# Main.net
KiCad netlist of a schematic drawn in Altium Designer
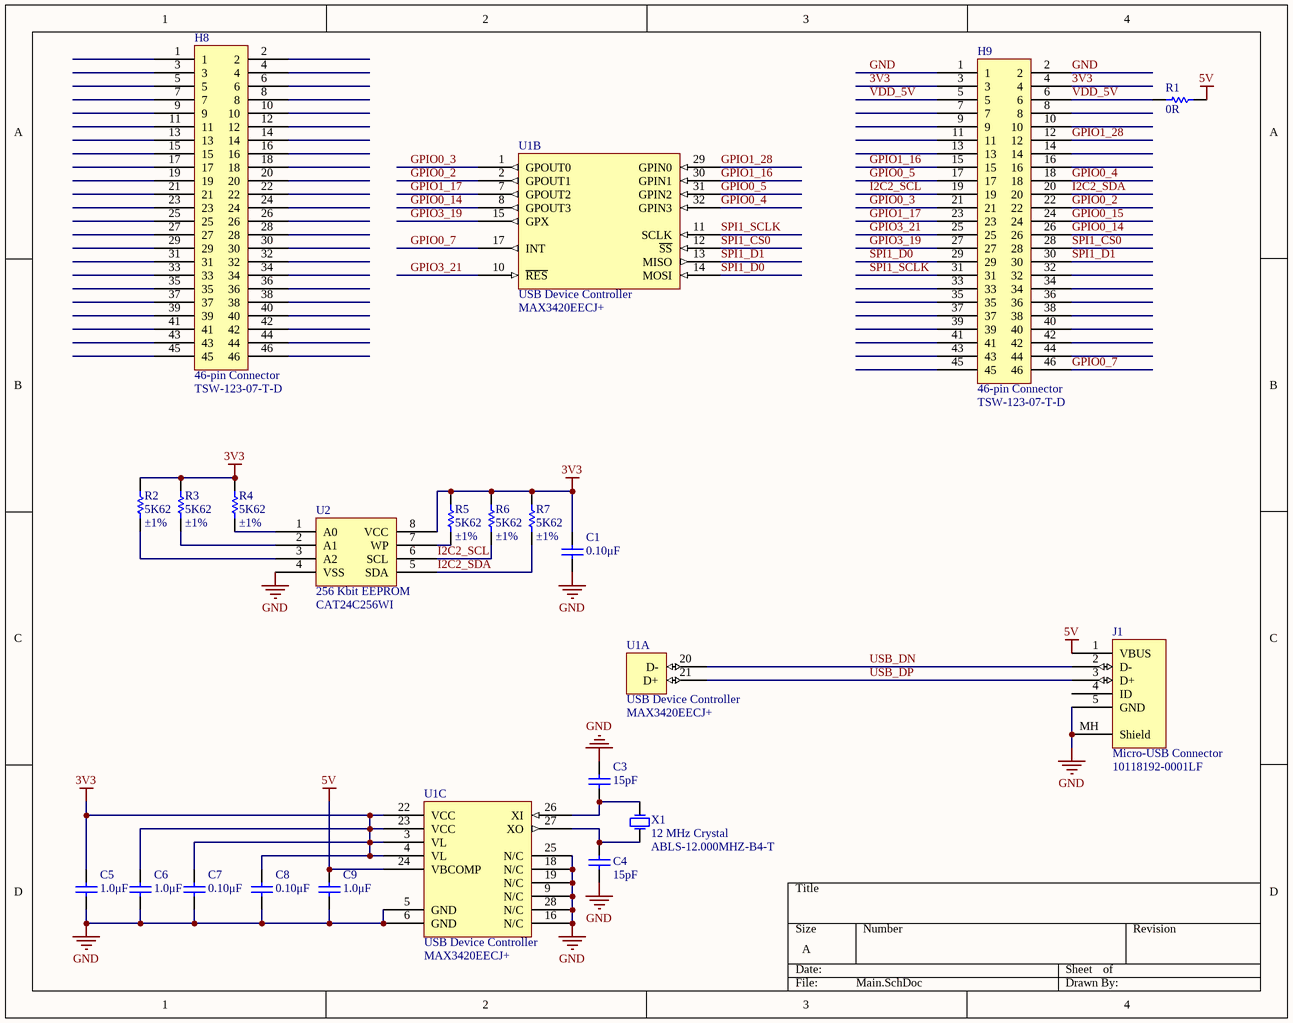
[diagram p0: Main.SchDoc]

(export (version "E")
  (design (tool "Eeschema 10.0.6"))
  (components
    (comp (ref "C1")
      (value "0.10μF")
      (footprint "0805_100")
      (description "CAP 0.10μF  0805 16V   ±10%    X7R")
      (fields (field (name "MANUFACTURER") "Murata") (field (name "PARTNUMBER") "GRM21BR71C104KA01#"))
      (libsource (lib "0805_Cap_GRM") (part "GRM21BR71C104KA01#"))
    )
    (comp (ref "C3")
      (value "15pF")
      (footprint "0805_100")
      (description "CAP 15pF     0805 250V  ±5%     C0G")
      (fields (field (name "MANUFACTURER") "Murata") (field (name "PARTNUMBER") "GRM21A5C2E150JW01#"))
      (libsource (lib "0805_Cap_GRM") (part "GRM21A5C2E150JW01#"))
    )
    (comp (ref "C4")
      (value "15pF")
      (footprint "0805_100")
      (description "CAP 15pF     0805 250V  ±5%     C0G")
      (fields (field (name "MANUFACTURER") "Murata") (field (name "PARTNUMBER") "GRM21A5C2E150JW01#"))
      (libsource (lib "0805_Cap_GRM") (part "GRM21A5C2E150JW01#"))
    )
    (comp (ref "C5")
      (value "1.0μF")
      (footprint "0805_100")
      (description "CAP 1.0μF   0805 16V   ±10%    X7R")
      (fields (field (name "MANUFACTURER") "Murata") (field (name "PARTNUMBER") "GRM21BR71C105KA01#"))
      (libsource (lib "0805_Cap_GRM") (part "GRM21BR71C105KA01#"))
    )
    (comp (ref "C6")
      (value "1.0μF")
      (footprint "0805_100")
      (description "CAP 1.0μF   0805 16V   ±10%    X7R")
      (fields (field (name "MANUFACTURER") "Murata") (field (name "PARTNUMBER") "GRM21BR71C105KA01#"))
      (libsource (lib "0805_Cap_GRM") (part "GRM21BR71C105KA01#"))
    )
    (comp (ref "C7")
      (value "0.10μF")
      (footprint "0805_100")
      (description "CAP 0.10μF  0805 16V   ±10%    X7R")
      (fields (field (name "MANUFACTURER") "Murata") (field (name "PARTNUMBER") "GRM21BR71C104KA01#"))
      (libsource (lib "0805_Cap_GRM") (part "GRM21BR71C104KA01#"))
    )
    (comp (ref "C8")
      (value "0.10μF")
      (footprint "0805_100")
      (description "CAP 0.10μF  0805 16V   ±10%    X7R")
      (fields (field (name "MANUFACTURER") "Murata") (field (name "PARTNUMBER") "GRM21BR71C104KA01#"))
      (libsource (lib "0805_Cap_GRM") (part "GRM21BR71C104KA01#"))
    )
    (comp (ref "C9")
      (value "1.0μF")
      (footprint "0805_100")
      (description "CAP 1.0μF   0805 16V   ±10%    X7R")
      (fields (field (name "MANUFACTURER") "Murata") (field (name "PARTNUMBER") "GRM21BR71C105KA01#"))
      (libsource (lib "0805_Cap_GRM") (part "GRM21BR71C105KA01#"))
    )
    (comp (ref "H8")
      (value "46-pin Connector")
      (footprint "TSW-123-07-X-S")
      (description "46-pin Dual Row 100-mil Headers")
      (fields (field (name "MANUFACTURER") "Samtec") (field (name "PARTNUMBER") "TSW-123-07-T-D"))
      (libsource (lib "Samtec") (part "TSW-123-07-T-D"))
    )
    (comp (ref "H9")
      (value "46-pin Connector")
      (footprint "TSW-123-07-X-S")
      (description "46-pin Dual Row 100-mil Headers")
      (fields (field (name "MANUFACTURER") "Samtec") (field (name "PARTNUMBER") "TSW-123-07-T-D"))
      (libsource (lib "Samtec") (part "TSW-123-07-T-D"))
    )
    (comp (ref "J1")
      (value "Micro-USB Connector")
      (footprint "10118192")
      (description "Surface-mount USB 2.0 Micro-B Connector with Flange")
      (fields (field (name "MANUFACTURER") "Amphenol") (field (name "PARTNUMBER") "10118192-0001LF"))
      (libsource (lib "Amphenol") (part "10118192-0001LF"))
    )
    (comp (ref "R1")
      (value "0R")
      (footprint "0805_75")
      (description "RES 0R 0805 2 A")
      (fields (field (name "PARTNUMBER") "ERJ-6GEY0R00V") (field (name "MANUFACTURER") "Panasonic"))
      (libsource (lib "0805_Res_ERJ") (part "ERJ-6GEY0R00V"))
    )
    (comp (ref "R2")
      (value "5K62")
      (footprint "0805_75")
      (description "RES 5K62 0805 ±1%")
      (fields
        (field (name "PARTNUMBER") "ERJ-6ENF5621V")
        (field (name "MANUFACTURER") "Panasonic")
        (field (name "TOLERANCE") "±1%")
      )
      (libsource (lib "0805_Res_ERJ") (part "ERJ-6ENF5621V"))
    )
    (comp (ref "R3")
      (value "5K62")
      (footprint "0805_75")
      (description "RES 5K62 0805 ±1%")
      (fields
        (field (name "PARTNUMBER") "ERJ-6ENF5621V")
        (field (name "MANUFACTURER") "Panasonic")
        (field (name "TOLERANCE") "±1%")
      )
      (libsource (lib "0805_Res_ERJ") (part "ERJ-6ENF5621V"))
    )
    (comp (ref "R4")
      (value "5K62")
      (footprint "0805_75")
      (description "RES 5K62 0805 ±1%")
      (fields
        (field (name "PARTNUMBER") "ERJ-6ENF5621V")
        (field (name "MANUFACTURER") "Panasonic")
        (field (name "TOLERANCE") "±1%")
      )
      (libsource (lib "0805_Res_ERJ") (part "ERJ-6ENF5621V"))
    )
    (comp (ref "R5")
      (value "5K62")
      (footprint "0805_75")
      (description "RES 5K62 0805 ±1%")
      (fields
        (field (name "PARTNUMBER") "ERJ-6ENF5621V")
        (field (name "MANUFACTURER") "Panasonic")
        (field (name "TOLERANCE") "±1%")
      )
      (libsource (lib "0805_Res_ERJ") (part "ERJ-6ENF5621V"))
    )
    (comp (ref "R6")
      (value "5K62")
      (footprint "0805_75")
      (description "RES 5K62 0805 ±1%")
      (fields
        (field (name "PARTNUMBER") "ERJ-6ENF5621V")
        (field (name "MANUFACTURER") "Panasonic")
        (field (name "TOLERANCE") "±1%")
      )
      (libsource (lib "0805_Res_ERJ") (part "ERJ-6ENF5621V"))
    )
    (comp (ref "R7")
      (value "5K62")
      (footprint "0805_75")
      (description "RES 5K62 0805 ±1%")
      (fields
        (field (name "PARTNUMBER") "ERJ-6ENF5621V")
        (field (name "MANUFACTURER") "Panasonic")
        (field (name "TOLERANCE") "±1%")
      )
      (libsource (lib "0805_Res_ERJ") (part "ERJ-6ENF5621V"))
    )
    (comp (ref "U1")
      (value "USB Device Controller")
      (footprint "C32+1")
      (description "USB Peripheral Controller with SPI Interface")
      (fields (field (name "MANUFACTURER") "Maxim IC") (field (name "PARTNUMBER") "MAX3420EECJ+"))
      (libsource (lib "Maxim") (part "MAX3420EEJC+"))
    )
    (comp (ref "U2")
      (value "256 Kbit EEPROM")
      (footprint "SOIC-8")
      (description "256 Kbit EEPROM Memory - I2C")
      (fields (field (name "MANUFACTURER") "ON-Semiconductor") (field (name "PARTNUMBER") "CAT24C256WI"))
      (libsource (lib "OnSemi") (part "CAT24C256WI"))
    )
    (comp (ref "X1")
      (value "12 MHz Crystal")
      (footprint "ABLS")
      (description "12 MHz 20 ppm Crystal")
      (fields (field (name "MANUFACTURER") "Abracon") (field (name "PARTNUMBER") "ABLS-12.000MHZ-B4-T"))
      (libsource (lib "Abracon") (part "ABLS-12.000MHZ-B4-T"))
    )
  )
  (nets
    (net (code "1") (name "/GPIO0_2") (class "Default")
      (node (ref "H9") (pin "22") (pinfunction "22_22") (pintype "passive"))
      (node (ref "U1") (pin "2") (pinfunction "GPOUT1_2") (pintype "output"))
    )
    (net (code "2") (name "/GPIO0_3") (class "Default")
      (node (ref "H9") (pin "21") (pinfunction "21_21") (pintype "passive"))
      (node (ref "U1") (pin "1") (pinfunction "GPOUT0_1") (pintype "output"))
    )
    (net (code "3") (name "/GPIO0_4") (class "Default")
      (node (ref "H9") (pin "18") (pinfunction "18_18") (pintype "passive"))
      (node (ref "U1") (pin "32") (pinfunction "GPIN3_32") (pintype "input"))
    )
    (net (code "4") (name "/GPIO0_5") (class "Default")
      (node (ref "H9") (pin "17") (pinfunction "17_17") (pintype "passive"))
      (node (ref "U1") (pin "31") (pinfunction "GPIN2_31") (pintype "input"))
    )
    (net (code "5") (name "/GPIO0_7") (class "Default")
      (node (ref "H9") (pin "46") (pinfunction "46_46") (pintype "passive"))
      (node (ref "U1") (pin "17") (pinfunction "INT_17") (pintype "output"))
    )
    (net (code "6") (name "/GPIO0_14") (class "Default")
      (node (ref "H9") (pin "26") (pinfunction "26_26") (pintype "passive"))
      (node (ref "U1") (pin "8") (pinfunction "GPOUT3_8") (pintype "output"))
    )
    (net (code "7") (name "/GPIO0_15") (class "Default")
      (node (ref "H9") (pin "24") (pinfunction "24_24") (pintype "passive"))
    )
    (net (code "8") (name "/GPIO1_16") (class "Default")
      (node (ref "H9") (pin "15") (pinfunction "15_15") (pintype "passive"))
      (node (ref "U1") (pin "30") (pinfunction "GPIN1_30") (pintype "input"))
    )
    (net (code "9") (name "/GPIO1_17") (class "Default")
      (node (ref "H9") (pin "23") (pinfunction "23_23") (pintype "passive"))
      (node (ref "U1") (pin "7") (pinfunction "GPOUT2_7") (pintype "output"))
    )
    (net (code "10") (name "/GPIO1_28") (class "Default")
      (node (ref "H9") (pin "12") (pinfunction "12_12") (pintype "passive"))
      (node (ref "U1") (pin "29") (pinfunction "GPIN0_29") (pintype "input"))
    )
    (net (code "11") (name "/GPIO3_19") (class "Default")
      (node (ref "H9") (pin "27") (pinfunction "27_27") (pintype "passive"))
      (node (ref "U1") (pin "15") (pinfunction "GPX_15") (pintype "output"))
    )
    (net (code "12") (name "/GPIO3_21") (class "Default")
      (node (ref "H9") (pin "25") (pinfunction "25_25") (pintype "passive"))
      (node (ref "U1") (pin "10") (pinfunction "~{RES}_10") (pintype "input"))
    )
    (net (code "13") (name "/I2C2_SCL") (class "Default")
      (node (ref "H9") (pin "19") (pinfunction "19_19") (pintype "passive"))
      (node (ref "R6") (pin "1") (pinfunction "1_1") (pintype "passive"))
      (node (ref "U2") (pin "6") (pinfunction "SCL_6") (pintype "passive"))
    )
    (net (code "14") (name "/I2C2_SDA") (class "Default")
      (node (ref "H9") (pin "20") (pinfunction "20_20") (pintype "passive"))
      (node (ref "R7") (pin "1") (pinfunction "1_1") (pintype "passive"))
      (node (ref "U2") (pin "5") (pinfunction "SDA_5") (pintype "passive"))
    )
    (net (code "15") (name "/SPI1_CS0") (class "Default")
      (node (ref "H9") (pin "28") (pinfunction "28_28") (pintype "passive"))
      (node (ref "U1") (pin "12") (pinfunction "~{SS}_12") (pintype "input"))
    )
    (net (code "16") (name "/SPI1_D0") (class "Default")
      (node (ref "H9") (pin "29") (pinfunction "29_29") (pintype "passive"))
      (node (ref "U1") (pin "14") (pinfunction "MOSI_14") (pintype "input"))
    )
    (net (code "17") (name "/SPI1_D1") (class "Default")
      (node (ref "H9") (pin "30") (pinfunction "30_30") (pintype "passive"))
      (node (ref "U1") (pin "13") (pinfunction "MISO_13") (pintype "output"))
    )
    (net (code "18") (name "/SPI1_SCLK") (class "Default")
      (node (ref "H9") (pin "31") (pinfunction "31_31") (pintype "passive"))
      (node (ref "U1") (pin "11") (pinfunction "SCLK_11") (pintype "input"))
    )
    (net (code "19") (name "/USB_DN") (class "Default")
      (node (ref "J1") (pin "2") (pinfunction "D-_2") (pintype "bidirectional"))
      (node (ref "U1") (pin "20") (pinfunction "D-_20") (pintype "bidirectional"))
    )
    (net (code "20") (name "/USB_DP") (class "Default")
      (node (ref "J1") (pin "3") (pinfunction "D+_3") (pintype "bidirectional"))
      (node (ref "U1") (pin "21") (pinfunction "D+_21") (pintype "bidirectional"))
    )
    (net (code "21") (name "/VDD_5V") (class "Default")
      (node (ref "H9") (pin "5") (pinfunction "5_5") (pintype "passive"))
      (node (ref "H9") (pin "6") (pinfunction "6_6") (pintype "passive"))
      (node (ref "R1") (pin "2") (pinfunction "2_2") (pintype "passive"))
    )
    (net (code "22") (name "3V3") (class "Default")
      (node (ref "C1") (pin "2") (pinfunction "2_2") (pintype "passive"))
      (node (ref "C5") (pin "2") (pinfunction "2_2") (pintype "passive"))
      (node (ref "C6") (pin "2") (pinfunction "2_2") (pintype "passive"))
      (node (ref "C7") (pin "2") (pinfunction "2_2") (pintype "passive"))
      (node (ref "C8") (pin "2") (pinfunction "2_2") (pintype "passive"))
      (node (ref "H9") (pin "3") (pinfunction "3_3") (pintype "passive"))
      (node (ref "H9") (pin "4") (pinfunction "4_4") (pintype "passive"))
      (node (ref "R2") (pin "2") (pinfunction "2_2") (pintype "passive"))
      (node (ref "R3") (pin "2") (pinfunction "2_2") (pintype "passive"))
      (node (ref "R4") (pin "2") (pinfunction "2_2") (pintype "passive"))
      (node (ref "R5") (pin "2") (pinfunction "2_2") (pintype "passive"))
      (node (ref "R6") (pin "2") (pinfunction "2_2") (pintype "passive"))
      (node (ref "R7") (pin "2") (pinfunction "2_2") (pintype "passive"))
      (node (ref "U1") (pin "22") (pinfunction "VCC_22") (pintype "power_in"))
      (node (ref "U1") (pin "23") (pinfunction "VCC_23") (pintype "power_in"))
      (node (ref "U1") (pin "3") (pinfunction "VL_3") (pintype "power_in"))
      (node (ref "U1") (pin "4") (pinfunction "VL_4") (pintype "power_in"))
      (node (ref "U2") (pin "8") (pinfunction "VCC_8") (pintype "passive"))
    )
    (net (code "23") (name "5V") (class "Default")
      (node (ref "C9") (pin "2") (pinfunction "2_2") (pintype "passive"))
      (node (ref "J1") (pin "1") (pinfunction "VBUS_1") (pintype "power_in"))
      (node (ref "R1") (pin "1") (pinfunction "1_1") (pintype "passive"))
      (node (ref "U1") (pin "24") (pinfunction "VBCOMP_24") (pintype "power_in"))
    )
    (net (code "24") (name "GND") (class "Default")
      (node (ref "C1") (pin "1") (pinfunction "1_1") (pintype "passive"))
      (node (ref "C3") (pin "2") (pinfunction "2_2") (pintype "passive"))
      (node (ref "C4") (pin "1") (pinfunction "1_1") (pintype "passive"))
      (node (ref "C5") (pin "1") (pinfunction "1_1") (pintype "passive"))
      (node (ref "C6") (pin "1") (pinfunction "1_1") (pintype "passive"))
      (node (ref "C7") (pin "1") (pinfunction "1_1") (pintype "passive"))
      (node (ref "C8") (pin "1") (pinfunction "1_1") (pintype "passive"))
      (node (ref "C9") (pin "1") (pinfunction "1_1") (pintype "passive"))
      (node (ref "H9") (pin "1") (pinfunction "1_1") (pintype "passive"))
      (node (ref "H9") (pin "2") (pinfunction "2_2") (pintype "passive"))
      (node (ref "J1") (pin "5") (pinfunction "GND_5") (pintype "power_in"))
      (node (ref "J1") (pin "MH") (pinfunction "Shield_MH") (pintype "passive"))
      (node (ref "U1") (pin "16") (pinfunction "N/C_16") (pintype "passive"))
      (node (ref "U1") (pin "18") (pinfunction "N/C_18") (pintype "passive"))
      (node (ref "U1") (pin "19") (pinfunction "N/C_19") (pintype "passive"))
      (node (ref "U1") (pin "25") (pinfunction "N/C_25") (pintype "passive"))
      (node (ref "U1") (pin "28") (pinfunction "N/C_28") (pintype "passive"))
      (node (ref "U1") (pin "5") (pinfunction "GND_5") (pintype "power_in"))
      (node (ref "U1") (pin "6") (pinfunction "GND_6") (pintype "power_in"))
      (node (ref "U1") (pin "9") (pinfunction "N/C_9") (pintype "passive"))
      (node (ref "U2") (pin "4") (pinfunction "VSS_4") (pintype "passive"))
    )
    (net (code "25") (name "Net-(U1C-XI)") (class "Default")
      (node (ref "C3") (pin "1") (pinfunction "1_1") (pintype "passive"))
      (node (ref "U1") (pin "26") (pinfunction "XI_26") (pintype "input"))
      (node (ref "X1") (pin "2") (pinfunction "X2_2") (pintype "passive"))
    )
    (net (code "26") (name "Net-(U1C-XO)") (class "Default")
      (node (ref "C4") (pin "2") (pinfunction "2_2") (pintype "passive"))
      (node (ref "U1") (pin "27") (pinfunction "XO_27") (pintype "output"))
      (node (ref "X1") (pin "1") (pinfunction "X1_1") (pintype "passive"))
    )
    (net (code "27") (name "Net-(U2-A0)") (class "Default")
      (node (ref "R4") (pin "1") (pinfunction "1_1") (pintype "passive"))
      (node (ref "U2") (pin "1") (pinfunction "A0_1") (pintype "passive"))
    )
    (net (code "28") (name "Net-(U2-A1)") (class "Default")
      (node (ref "R3") (pin "1") (pinfunction "1_1") (pintype "passive"))
      (node (ref "U2") (pin "2") (pinfunction "A1_2") (pintype "passive"))
    )
    (net (code "29") (name "Net-(U2-A2)") (class "Default")
      (node (ref "R2") (pin "1") (pinfunction "1_1") (pintype "passive"))
      (node (ref "U2") (pin "3") (pinfunction "A2_3") (pintype "passive"))
    )
    (net (code "30") (name "Net-(U2-WP)") (class "Default")
      (node (ref "R5") (pin "1") (pinfunction "1_1") (pintype "passive"))
      (node (ref "U2") (pin "7") (pinfunction "WP_7") (pintype "passive"))
    )
    (net (code "31") (name "unconnected-(H8-Pad1)") (class "Default")
      (node (ref "H8") (pin "1") (pinfunction "1_1") (pintype "passive"))
    )
    (net (code "32") (name "unconnected-(H8-Pad2)") (class "Default")
      (node (ref "H8") (pin "2") (pinfunction "2_2") (pintype "passive"))
    )
    (net (code "33") (name "unconnected-(H8-Pad3)") (class "Default")
      (node (ref "H8") (pin "3") (pinfunction "3_3") (pintype "passive"))
    )
    (net (code "34") (name "unconnected-(H8-Pad4)") (class "Default")
      (node (ref "H8") (pin "4") (pinfunction "4_4") (pintype "passive"))
    )
    (net (code "35") (name "unconnected-(H8-Pad5)") (class "Default")
      (node (ref "H8") (pin "5") (pinfunction "5_5") (pintype "passive"))
    )
    (net (code "36") (name "unconnected-(H8-Pad6)") (class "Default")
      (node (ref "H8") (pin "6") (pinfunction "6_6") (pintype "passive"))
    )
    (net (code "37") (name "unconnected-(H8-Pad7)") (class "Default")
      (node (ref "H8") (pin "7") (pinfunction "7_7") (pintype "passive"))
    )
    (net (code "38") (name "unconnected-(H8-Pad8)") (class "Default")
      (node (ref "H8") (pin "8") (pinfunction "8_8") (pintype "passive"))
    )
    (net (code "39") (name "unconnected-(H8-Pad9)") (class "Default")
      (node (ref "H8") (pin "9") (pinfunction "9_9") (pintype "passive"))
    )
    (net (code "40") (name "unconnected-(H8-Pad10)") (class "Default")
      (node (ref "H8") (pin "10") (pinfunction "10_10") (pintype "passive"))
    )
    (net (code "41") (name "unconnected-(H8-Pad11)") (class "Default")
      (node (ref "H8") (pin "11") (pinfunction "11_11") (pintype "passive"))
    )
    (net (code "42") (name "unconnected-(H8-Pad12)") (class "Default")
      (node (ref "H8") (pin "12") (pinfunction "12_12") (pintype "passive"))
    )
    (net (code "43") (name "unconnected-(H8-Pad13)") (class "Default")
      (node (ref "H8") (pin "13") (pinfunction "13_13") (pintype "passive"))
    )
    (net (code "44") (name "unconnected-(H8-Pad14)") (class "Default")
      (node (ref "H8") (pin "14") (pinfunction "14_14") (pintype "passive"))
    )
    (net (code "45") (name "unconnected-(H8-Pad15)") (class "Default")
      (node (ref "H8") (pin "15") (pinfunction "15_15") (pintype "passive"))
    )
    (net (code "46") (name "unconnected-(H8-Pad16)") (class "Default")
      (node (ref "H8") (pin "16") (pinfunction "16_16") (pintype "passive"))
    )
    (net (code "47") (name "unconnected-(H8-Pad17)") (class "Default")
      (node (ref "H8") (pin "17") (pinfunction "17_17") (pintype "passive"))
    )
    (net (code "48") (name "unconnected-(H8-Pad18)") (class "Default")
      (node (ref "H8") (pin "18") (pinfunction "18_18") (pintype "passive"))
    )
    (net (code "49") (name "unconnected-(H8-Pad19)") (class "Default")
      (node (ref "H8") (pin "19") (pinfunction "19_19") (pintype "passive"))
    )
    (net (code "50") (name "unconnected-(H8-Pad20)") (class "Default")
      (node (ref "H8") (pin "20") (pinfunction "20_20") (pintype "passive"))
    )
    (net (code "51") (name "unconnected-(H8-Pad21)") (class "Default")
      (node (ref "H8") (pin "21") (pinfunction "21_21") (pintype "passive"))
    )
    (net (code "52") (name "unconnected-(H8-Pad22)") (class "Default")
      (node (ref "H8") (pin "22") (pinfunction "22_22") (pintype "passive"))
    )
    (net (code "53") (name "unconnected-(H8-Pad23)") (class "Default")
      (node (ref "H8") (pin "23") (pinfunction "23_23") (pintype "passive"))
    )
    (net (code "54") (name "unconnected-(H8-Pad24)") (class "Default")
      (node (ref "H8") (pin "24") (pinfunction "24_24") (pintype "passive"))
    )
    (net (code "55") (name "unconnected-(H8-Pad25)") (class "Default")
      (node (ref "H8") (pin "25") (pinfunction "25_25") (pintype "passive"))
    )
    (net (code "56") (name "unconnected-(H8-Pad26)") (class "Default")
      (node (ref "H8") (pin "26") (pinfunction "26_26") (pintype "passive"))
    )
    (net (code "57") (name "unconnected-(H8-Pad27)") (class "Default")
      (node (ref "H8") (pin "27") (pinfunction "27_27") (pintype "passive"))
    )
    (net (code "58") (name "unconnected-(H8-Pad28)") (class "Default")
      (node (ref "H8") (pin "28") (pinfunction "28_28") (pintype "passive"))
    )
    (net (code "59") (name "unconnected-(H8-Pad29)") (class "Default")
      (node (ref "H8") (pin "29") (pinfunction "29_29") (pintype "passive"))
    )
    (net (code "60") (name "unconnected-(H8-Pad30)") (class "Default")
      (node (ref "H8") (pin "30") (pinfunction "30_30") (pintype "passive"))
    )
    (net (code "61") (name "unconnected-(H8-Pad31)") (class "Default")
      (node (ref "H8") (pin "31") (pinfunction "31_31") (pintype "passive"))
    )
    (net (code "62") (name "unconnected-(H8-Pad32)") (class "Default")
      (node (ref "H8") (pin "32") (pinfunction "32_32") (pintype "passive"))
    )
    (net (code "63") (name "unconnected-(H8-Pad33)") (class "Default")
      (node (ref "H8") (pin "33") (pinfunction "33_33") (pintype "passive"))
    )
    (net (code "64") (name "unconnected-(H8-Pad34)") (class "Default")
      (node (ref "H8") (pin "34") (pinfunction "34_34") (pintype "passive"))
    )
    (net (code "65") (name "unconnected-(H8-Pad35)") (class "Default")
      (node (ref "H8") (pin "35") (pinfunction "35_35") (pintype "passive"))
    )
    (net (code "66") (name "unconnected-(H8-Pad36)") (class "Default")
      (node (ref "H8") (pin "36") (pinfunction "36_36") (pintype "passive"))
    )
    (net (code "67") (name "unconnected-(H8-Pad37)") (class "Default")
      (node (ref "H8") (pin "37") (pinfunction "37_37") (pintype "passive"))
    )
    (net (code "68") (name "unconnected-(H8-Pad38)") (class "Default")
      (node (ref "H8") (pin "38") (pinfunction "38_38") (pintype "passive"))
    )
    (net (code "69") (name "unconnected-(H8-Pad39)") (class "Default")
      (node (ref "H8") (pin "39") (pinfunction "39_39") (pintype "passive"))
    )
    (net (code "70") (name "unconnected-(H8-Pad40)") (class "Default")
      (node (ref "H8") (pin "40") (pinfunction "40_40") (pintype "passive"))
    )
    (net (code "71") (name "unconnected-(H8-Pad41)") (class "Default")
      (node (ref "H8") (pin "41") (pinfunction "41_41") (pintype "passive"))
    )
    (net (code "72") (name "unconnected-(H8-Pad42)") (class "Default")
      (node (ref "H8") (pin "42") (pinfunction "42_42") (pintype "passive"))
    )
    (net (code "73") (name "unconnected-(H8-Pad43)") (class "Default")
      (node (ref "H8") (pin "43") (pinfunction "43_43") (pintype "passive"))
    )
    (net (code "74") (name "unconnected-(H8-Pad44)") (class "Default")
      (node (ref "H8") (pin "44") (pinfunction "44_44") (pintype "passive"))
    )
    (net (code "75") (name "unconnected-(H8-Pad45)") (class "Default")
      (node (ref "H8") (pin "45") (pinfunction "45_45") (pintype "passive"))
    )
    (net (code "76") (name "unconnected-(H8-Pad46)") (class "Default")
      (node (ref "H8") (pin "46") (pinfunction "46_46") (pintype "passive"))
    )
    (net (code "77") (name "unconnected-(H9-Pad7)") (class "Default")
      (node (ref "H9") (pin "7") (pinfunction "7_7") (pintype "passive"))
    )
    (net (code "78") (name "unconnected-(H9-Pad8)") (class "Default")
      (node (ref "H9") (pin "8") (pinfunction "8_8") (pintype "passive"))
    )
    (net (code "79") (name "unconnected-(H9-Pad9)") (class "Default")
      (node (ref "H9") (pin "9") (pinfunction "9_9") (pintype "passive"))
    )
    (net (code "80") (name "unconnected-(H9-Pad10)") (class "Default")
      (node (ref "H9") (pin "10") (pinfunction "10_10") (pintype "passive"))
    )
    (net (code "81") (name "unconnected-(H9-Pad11)") (class "Default")
      (node (ref "H9") (pin "11") (pinfunction "11_11") (pintype "passive"))
    )
    (net (code "82") (name "unconnected-(H9-Pad13)") (class "Default")
      (node (ref "H9") (pin "13") (pinfunction "13_13") (pintype "passive"))
    )
    (net (code "83") (name "unconnected-(H9-Pad14)") (class "Default")
      (node (ref "H9") (pin "14") (pinfunction "14_14") (pintype "passive"))
    )
    (net (code "84") (name "unconnected-(H9-Pad16)") (class "Default")
      (node (ref "H9") (pin "16") (pinfunction "16_16") (pintype "passive"))
    )
    (net (code "85") (name "unconnected-(H9-Pad32)") (class "Default")
      (node (ref "H9") (pin "32") (pinfunction "32_32") (pintype "passive"))
    )
    (net (code "86") (name "unconnected-(H9-Pad33)") (class "Default")
      (node (ref "H9") (pin "33") (pinfunction "33_33") (pintype "passive"))
    )
    (net (code "87") (name "unconnected-(H9-Pad34)") (class "Default")
      (node (ref "H9") (pin "34") (pinfunction "34_34") (pintype "passive"))
    )
    (net (code "88") (name "unconnected-(H9-Pad35)") (class "Default")
      (node (ref "H9") (pin "35") (pinfunction "35_35") (pintype "passive"))
    )
    (net (code "89") (name "unconnected-(H9-Pad36)") (class "Default")
      (node (ref "H9") (pin "36") (pinfunction "36_36") (pintype "passive"))
    )
    (net (code "90") (name "unconnected-(H9-Pad37)") (class "Default")
      (node (ref "H9") (pin "37") (pinfunction "37_37") (pintype "passive"))
    )
    (net (code "91") (name "unconnected-(H9-Pad38)") (class "Default")
      (node (ref "H9") (pin "38") (pinfunction "38_38") (pintype "passive"))
    )
    (net (code "92") (name "unconnected-(H9-Pad39)") (class "Default")
      (node (ref "H9") (pin "39") (pinfunction "39_39") (pintype "passive"))
    )
    (net (code "93") (name "unconnected-(H9-Pad40)") (class "Default")
      (node (ref "H9") (pin "40") (pinfunction "40_40") (pintype "passive"))
    )
    (net (code "94") (name "unconnected-(H9-Pad41)") (class "Default")
      (node (ref "H9") (pin "41") (pinfunction "41_41") (pintype "passive"))
    )
    (net (code "95") (name "unconnected-(H9-Pad42)") (class "Default")
      (node (ref "H9") (pin "42") (pinfunction "42_42") (pintype "passive"))
    )
    (net (code "96") (name "unconnected-(H9-Pad43)") (class "Default")
      (node (ref "H9") (pin "43") (pinfunction "43_43") (pintype "passive"))
    )
    (net (code "97") (name "unconnected-(H9-Pad44)") (class "Default")
      (node (ref "H9") (pin "44") (pinfunction "44_44") (pintype "passive"))
    )
    (net (code "98") (name "unconnected-(H9-Pad45)") (class "Default")
      (node (ref "H9") (pin "45") (pinfunction "45_45") (pintype "passive"))
    )
    (net (code "99") (name "unconnected-(J1-ID-Pad4)") (class "Default")
      (node (ref "J1") (pin "4") (pinfunction "ID_4") (pintype "passive"))
    )
  )
)
